# OmerFaroukMACHMOUTLAR0098.net
KiCad netlist of a schematic drawn in EAGLE
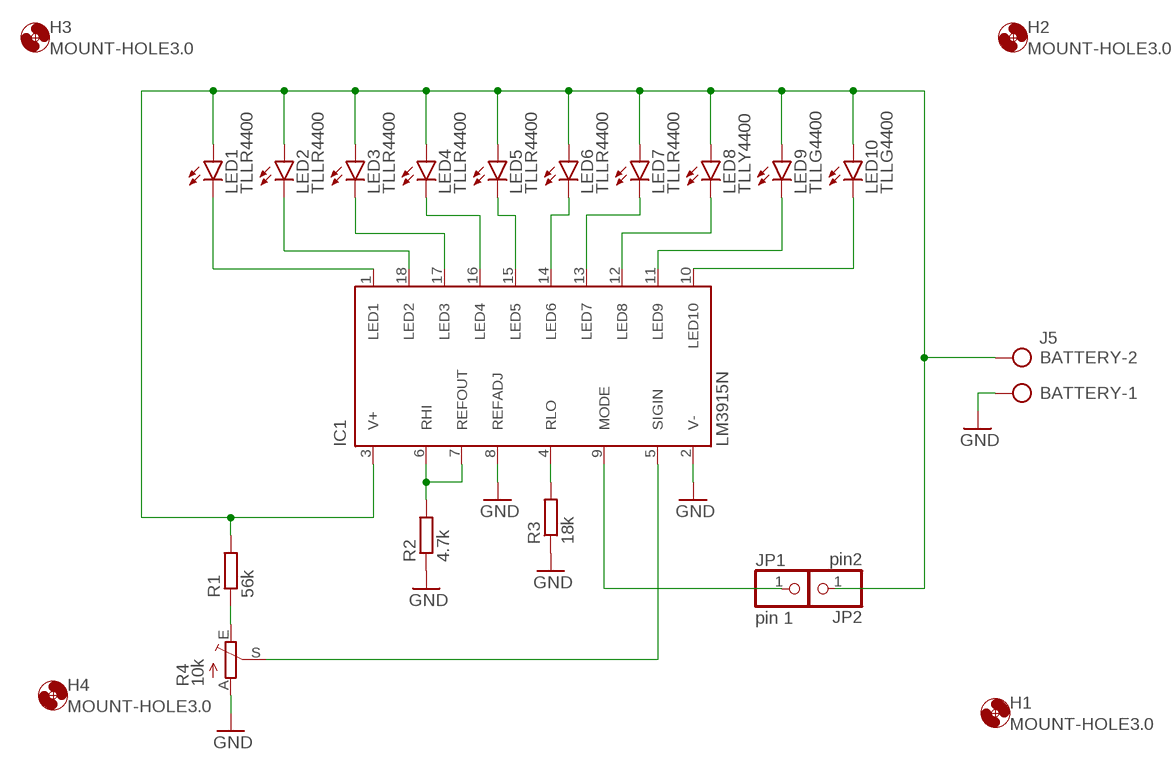
[diagram p0: schematic, sheet 1]

(export (version "E")
  (design (tool "Eeschema 10.0.6"))
  (components
    (comp (ref "BATTERY")
      (value "J5")
      (footprint "eagle-import:AK500_2")
      (libsource (lib "eagle-import") (part "AK500/2"))
    )
    (comp (ref "H1")
      (value "MOUNT-HOLE3.0")
      (footprint "eagle-import:3,0")
      (libsource (lib "eagle-import") (part "MOUNT-HOLE3.0"))
    )
    (comp (ref "H2")
      (value "MOUNT-HOLE3.0")
      (footprint "eagle-import:3,0")
      (libsource (lib "eagle-import") (part "MOUNT-HOLE3.0"))
    )
    (comp (ref "H3")
      (value "MOUNT-HOLE3.0")
      (footprint "eagle-import:3,0")
      (libsource (lib "eagle-import") (part "MOUNT-HOLE3.0"))
    )
    (comp (ref "H4")
      (value "MOUNT-HOLE3.0")
      (footprint "eagle-import:3,0")
      (libsource (lib "eagle-import") (part "MOUNT-HOLE3.0"))
    )
    (comp (ref "IC1")
      (value "LM3915N")
      (footprint "eagle-import:DIL18")
      (libsource (lib "eagle-import") (part "LM391N5"))
    )
    (comp (ref "JP1")
      (value "pin 1")
      (footprint "eagle-import:1X01")
      (libsource (lib "eagle-import") (part "PINHD-1X1"))
    )
    (comp (ref "JP2")
      (value "pin2")
      (footprint "eagle-import:1X01")
      (libsource (lib "eagle-import") (part "PINHD-1X1"))
    )
    (comp (ref "LED1")
      (value "TLLR4400")
      (footprint "eagle-import:LED3MM")
      (fields (field (name "MF") "VISHAY SEMICONDUCTOR"))
      (libsource (lib "eagle-import") (part "TLLR4400"))
    )
    (comp (ref "LED2")
      (value "TLLR4400")
      (footprint "eagle-import:LED3MM")
      (fields (field (name "MF") "VISHAY SEMICONDUCTOR"))
      (libsource (lib "eagle-import") (part "TLLR4400"))
    )
    (comp (ref "LED3")
      (value "TLLR4400")
      (footprint "eagle-import:LED3MM")
      (fields (field (name "MF") "VISHAY SEMICONDUCTOR"))
      (libsource (lib "eagle-import") (part "TLLR4400"))
    )
    (comp (ref "LED4")
      (value "TLLR4400")
      (footprint "eagle-import:LED3MM")
      (fields (field (name "MF") "VISHAY SEMICONDUCTOR"))
      (libsource (lib "eagle-import") (part "TLLR4400"))
    )
    (comp (ref "LED5")
      (value "TLLR4400")
      (footprint "eagle-import:LED3MM")
      (fields (field (name "MF") "VISHAY SEMICONDUCTOR"))
      (libsource (lib "eagle-import") (part "TLLR4400"))
    )
    (comp (ref "LED6")
      (value "TLLR4400")
      (footprint "eagle-import:LED3MM")
      (fields (field (name "MF") "VISHAY SEMICONDUCTOR"))
      (libsource (lib "eagle-import") (part "TLLR4400"))
    )
    (comp (ref "LED7")
      (value "TLLR4400")
      (footprint "eagle-import:LED3MM")
      (fields (field (name "MF") "VISHAY SEMICONDUCTOR"))
      (libsource (lib "eagle-import") (part "TLLR4400"))
    )
    (comp (ref "LED8")
      (value "TLLY4400")
      (footprint "eagle-import:LED3MM")
      (fields (field (name "MF") "VISHAY SEMICONDUCTOR"))
      (libsource (lib "eagle-import") (part "TLLY4400"))
    )
    (comp (ref "LED9")
      (value "TLLG4400")
      (footprint "eagle-import:LED3MM")
      (fields (field (name "MF") "VISHAY SEMICONDUCTOR"))
      (libsource (lib "eagle-import") (part "TLLG4400"))
    )
    (comp (ref "LED10")
      (value "TLLG4400")
      (footprint "eagle-import:LED3MM")
      (fields (field (name "MF") "VISHAY SEMICONDUCTOR"))
      (libsource (lib "eagle-import") (part "TLLG4400"))
    )
    (comp (ref "R1")
      (value "56k")
      (footprint "eagle-import:0204_7")
      (libsource (lib "eagle-import") (part "R-EU_0204/7"))
    )
    (comp (ref "R2")
      (value "4.7k")
      (footprint "eagle-import:0204_7")
      (libsource (lib "eagle-import") (part "R-EU_0204/7"))
    )
    (comp (ref "R3")
      (value "18k")
      (footprint "eagle-import:0204_7")
      (libsource (lib "eagle-import") (part "R-EU_0204/7"))
    )
    (comp (ref "R4")
      (value "10k")
      (footprint "eagle-import:S64W")
      (libsource (lib "eagle-import") (part "TRIM_EU-S64W"))
    )
  )
  (nets
    (net (code "1") (name "GND") (class "Default")
      (node (ref "BATTERY") (pin "1") (pinfunction "KL_1") (pintype "passive"))
      (node (ref "IC1") (pin "2") (pinfunction "V-_2") (pintype "power_in"))
      (node (ref "IC1") (pin "8") (pinfunction "REFADJ_8") (pintype "passive"))
      (node (ref "R2") (pin "1") (pinfunction "1_1") (pintype "passive"))
      (node (ref "R3") (pin "1") (pinfunction "1_1") (pintype "passive"))
      (node (ref "R4") (pin "A") (pinfunction "A_A") (pintype "passive"))
    )
    (net (code "2") (name "Net-(BATTERYB-KL)") (class "Default")
      (node (ref "BATTERY") (pin "2") (pinfunction "KL_2") (pintype "passive"))
      (node (ref "IC1") (pin "3") (pinfunction "V+_3") (pintype "power_in"))
      (node (ref "JP2") (pin "1") (pinfunction "1_1") (pintype "passive"))
      (node (ref "LED1") (pin "A") (pinfunction "A_A") (pintype "passive"))
      (node (ref "LED10") (pin "A") (pinfunction "A_A") (pintype "passive"))
      (node (ref "LED2") (pin "A") (pinfunction "A_A") (pintype "passive"))
      (node (ref "LED3") (pin "A") (pinfunction "A_A") (pintype "passive"))
      (node (ref "LED4") (pin "A") (pinfunction "A_A") (pintype "passive"))
      (node (ref "LED5") (pin "A") (pinfunction "A_A") (pintype "passive"))
      (node (ref "LED6") (pin "A") (pinfunction "A_A") (pintype "passive"))
      (node (ref "LED7") (pin "A") (pinfunction "A_A") (pintype "passive"))
      (node (ref "LED8") (pin "A") (pinfunction "A_A") (pintype "passive"))
      (node (ref "LED9") (pin "A") (pinfunction "A_A") (pintype "passive"))
      (node (ref "R1") (pin "2") (pinfunction "2_2") (pintype "passive"))
    )
    (net (code "3") (name "Net-(IC1-LED1)") (class "Default")
      (node (ref "IC1") (pin "1") (pinfunction "LED1_1") (pintype "output"))
      (node (ref "LED1") (pin "K") (pinfunction "C_K") (pintype "passive"))
    )
    (net (code "4") (name "Net-(IC1-LED2)") (class "Default")
      (node (ref "IC1") (pin "18") (pinfunction "LED2_18") (pintype "output"))
      (node (ref "LED2") (pin "K") (pinfunction "C_K") (pintype "passive"))
    )
    (net (code "5") (name "Net-(IC1-LED3)") (class "Default")
      (node (ref "IC1") (pin "17") (pinfunction "LED3_17") (pintype "output"))
      (node (ref "LED3") (pin "K") (pinfunction "C_K") (pintype "passive"))
    )
    (net (code "6") (name "Net-(IC1-LED4)") (class "Default")
      (node (ref "IC1") (pin "16") (pinfunction "LED4_16") (pintype "output"))
      (node (ref "LED4") (pin "K") (pinfunction "C_K") (pintype "passive"))
    )
    (net (code "7") (name "Net-(IC1-LED5)") (class "Default")
      (node (ref "IC1") (pin "15") (pinfunction "LED5_15") (pintype "output"))
      (node (ref "LED5") (pin "K") (pinfunction "C_K") (pintype "passive"))
    )
    (net (code "8") (name "Net-(IC1-LED6)") (class "Default")
      (node (ref "IC1") (pin "14") (pinfunction "LED6_14") (pintype "output"))
      (node (ref "LED6") (pin "K") (pinfunction "C_K") (pintype "passive"))
    )
    (net (code "9") (name "Net-(IC1-LED7)") (class "Default")
      (node (ref "IC1") (pin "13") (pinfunction "LED7_13") (pintype "output"))
      (node (ref "LED7") (pin "K") (pinfunction "C_K") (pintype "passive"))
    )
    (net (code "10") (name "Net-(IC1-LED8)") (class "Default")
      (node (ref "IC1") (pin "12") (pinfunction "LED8_12") (pintype "output"))
      (node (ref "LED8") (pin "K") (pinfunction "C_K") (pintype "passive"))
    )
    (net (code "11") (name "Net-(IC1-LED9)") (class "Default")
      (node (ref "IC1") (pin "11") (pinfunction "LED9_11") (pintype "output"))
      (node (ref "LED9") (pin "K") (pinfunction "C_K") (pintype "passive"))
    )
    (net (code "12") (name "Net-(IC1-LED10)") (class "Default")
      (node (ref "IC1") (pin "10") (pinfunction "LED10_10") (pintype "output"))
      (node (ref "LED10") (pin "K") (pinfunction "C_K") (pintype "passive"))
    )
    (net (code "13") (name "Net-(IC1-MODE)") (class "Default")
      (node (ref "IC1") (pin "9") (pinfunction "MODE_9") (pintype "input"))
      (node (ref "JP1") (pin "1") (pinfunction "1_1") (pintype "passive"))
    )
    (net (code "14") (name "Net-(IC1-REFOUT)") (class "Default")
      (node (ref "IC1") (pin "6") (pinfunction "RHI_6") (pintype "input"))
      (node (ref "IC1") (pin "7") (pinfunction "REFOUT_7") (pintype "output"))
      (node (ref "R2") (pin "2") (pinfunction "2_2") (pintype "passive"))
    )
    (net (code "15") (name "Net-(IC1-RLO)") (class "Default")
      (node (ref "IC1") (pin "4") (pinfunction "RLO_4") (pintype "input"))
      (node (ref "R3") (pin "2") (pinfunction "2_2") (pintype "passive"))
    )
    (net (code "16") (name "Net-(IC1-SIGIN)") (class "Default")
      (node (ref "IC1") (pin "5") (pinfunction "SIGIN_5") (pintype "input"))
      (node (ref "R4") (pin "S") (pinfunction "S_S") (pintype "passive"))
    )
    (net (code "17") (name "Net-(R1-Pad1)") (class "Default")
      (node (ref "R1") (pin "1") (pinfunction "1_1") (pintype "passive"))
      (node (ref "R4") (pin "E") (pinfunction "E_E") (pintype "passive"))
    )
  )
)
